# shield.net
KiCad netlist of a schematic drawn in EAGLE
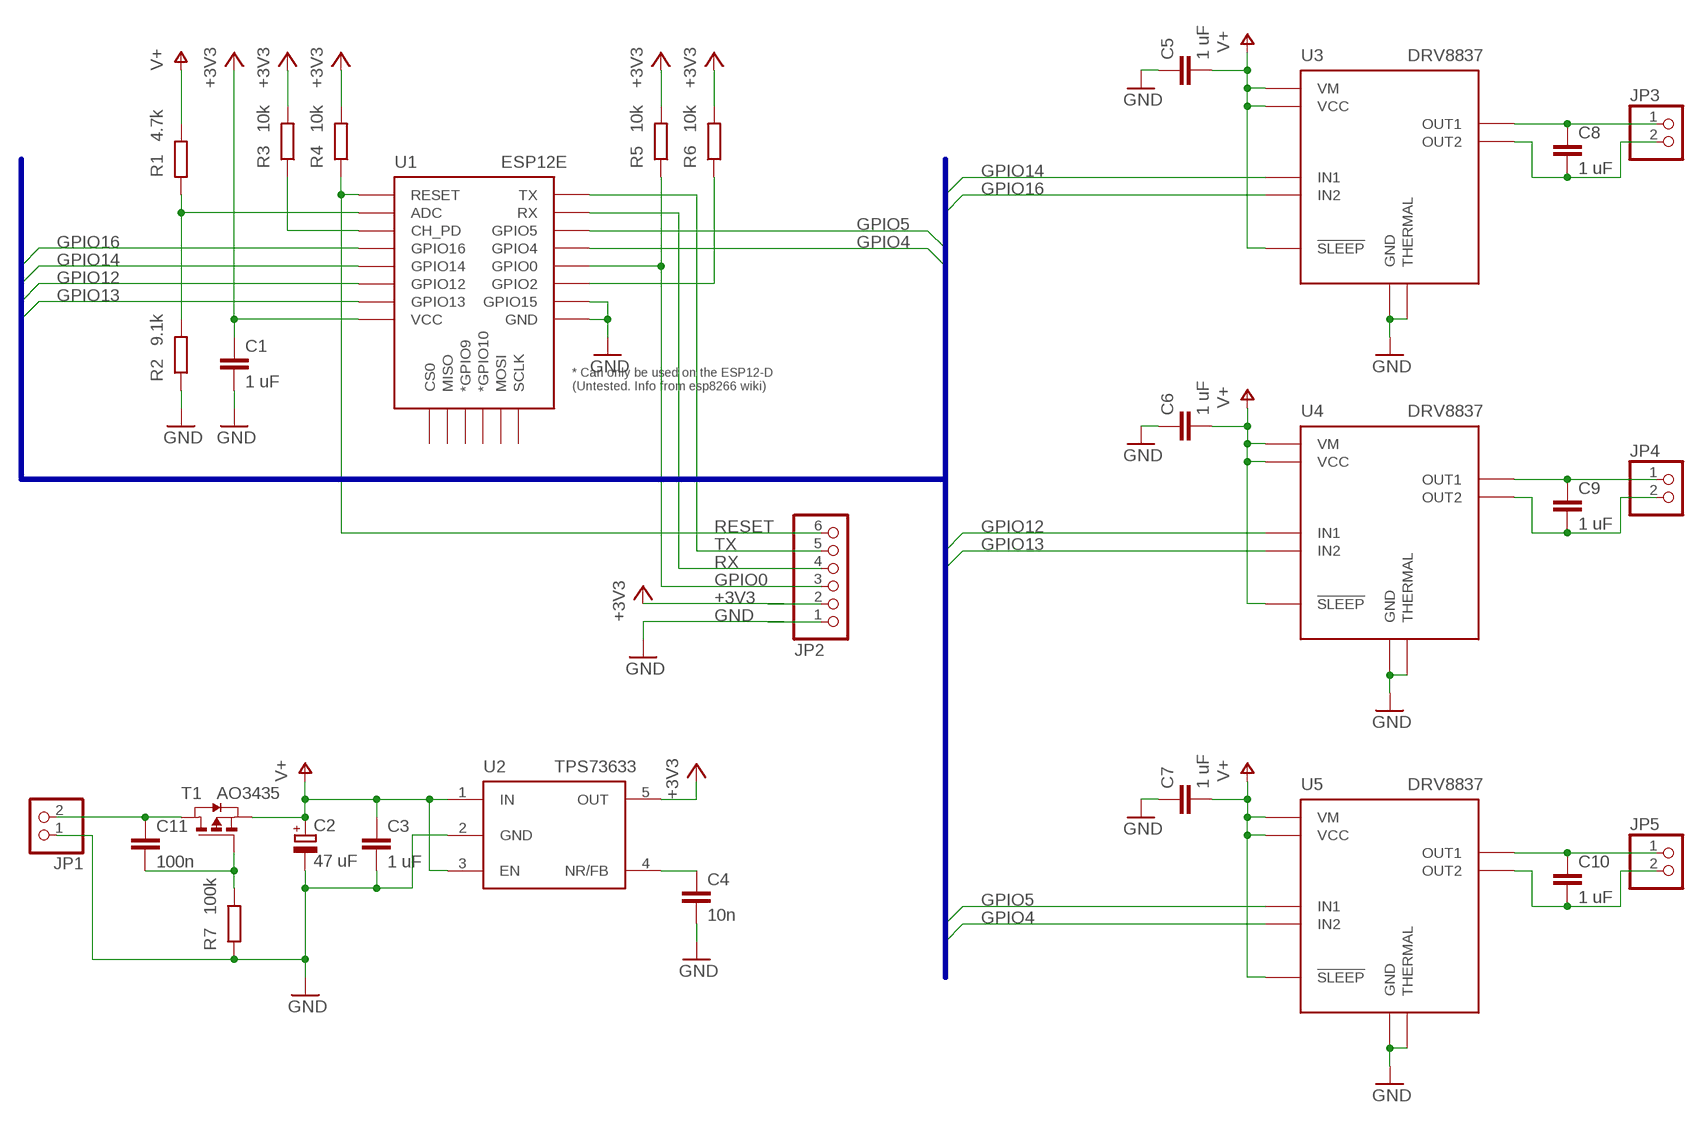
[diagram p0: schematic, sheet 1]

(export (version "E")
  (design (tool "Eeschema 10.0.6"))
  (components
    (comp (ref "C1")
      (value "1 uF")
      (footprint "eagle-import:C0805")
      (libsource (lib "eagle-import") (part "C-EUC0805"))
    )
    (comp (ref "C2")
      (value "47 uF")
      (footprint "eagle-import:SMC_A")
      (libsource (lib "eagle-import") (part "CPOL-EUSMCA"))
    )
    (comp (ref "C3")
      (value "1 uF")
      (footprint "eagle-import:C0805")
      (libsource (lib "eagle-import") (part "C-EUC0805"))
    )
    (comp (ref "C4")
      (value "10n")
      (footprint "eagle-import:C0603")
      (libsource (lib "eagle-import") (part "C-EUC0603"))
    )
    (comp (ref "C5")
      (value "1 uF")
      (footprint "eagle-import:C0805")
      (libsource (lib "eagle-import") (part "C-EUC0805"))
    )
    (comp (ref "C6")
      (value "1 uF")
      (footprint "eagle-import:C0805")
      (libsource (lib "eagle-import") (part "C-EUC0805"))
    )
    (comp (ref "C7")
      (value "1 uF")
      (footprint "eagle-import:C0805")
      (libsource (lib "eagle-import") (part "C-EUC0805"))
    )
    (comp (ref "C8")
      (value "1 uF")
      (footprint "eagle-import:C0805")
      (libsource (lib "eagle-import") (part "C-EUC0805"))
    )
    (comp (ref "C9")
      (value "1 uF")
      (footprint "eagle-import:C0805")
      (libsource (lib "eagle-import") (part "C-EUC0805"))
    )
    (comp (ref "C10")
      (value "1 uF")
      (footprint "eagle-import:C0805")
      (libsource (lib "eagle-import") (part "C-EUC0805"))
    )
    (comp (ref "C11")
      (value "100n")
      (footprint "eagle-import:C0603")
      (libsource (lib "eagle-import") (part "C-EUC0603"))
    )
    (comp (ref "JP1")
      (value "PINHD-1X2")
      (footprint "eagle-import:1X02")
      (libsource (lib "eagle-import") (part "PINHD-1X2"))
    )
    (comp (ref "JP2")
      (value "PINHD-1X6")
      (footprint "eagle-import:1X06")
      (libsource (lib "eagle-import") (part "PINHD-1X6"))
    )
    (comp (ref "JP3")
      (value "PINHD-1X2")
      (footprint "eagle-import:1X02")
      (libsource (lib "eagle-import") (part "PINHD-1X2"))
    )
    (comp (ref "JP4")
      (value "PINHD-1X2")
      (footprint "eagle-import:1X02")
      (libsource (lib "eagle-import") (part "PINHD-1X2"))
    )
    (comp (ref "JP5")
      (value "PINHD-1X2")
      (footprint "eagle-import:1X02")
      (libsource (lib "eagle-import") (part "PINHD-1X2"))
    )
    (comp (ref "R1")
      (value "4.7k")
      (footprint "eagle-import:R0603")
      (libsource (lib "eagle-import") (part "R-EU_R0603"))
    )
    (comp (ref "R2")
      (value "9.1k")
      (footprint "eagle-import:R0603")
      (libsource (lib "eagle-import") (part "R-EU_R0603"))
    )
    (comp (ref "R3")
      (value "10k")
      (footprint "eagle-import:R0603")
      (libsource (lib "eagle-import") (part "R-EU_R0603"))
    )
    (comp (ref "R4")
      (value "10k")
      (footprint "eagle-import:R0603")
      (libsource (lib "eagle-import") (part "R-EU_R0603"))
    )
    (comp (ref "R5")
      (value "10k")
      (footprint "eagle-import:R0603")
      (libsource (lib "eagle-import") (part "R-EU_R0603"))
    )
    (comp (ref "R6")
      (value "10k")
      (footprint "eagle-import:R0603")
      (libsource (lib "eagle-import") (part "R-EU_R0603"))
    )
    (comp (ref "R7")
      (value "100k")
      (footprint "eagle-import:R0603")
      (libsource (lib "eagle-import") (part "R-EU_R0603"))
    )
    (comp (ref "T1")
      (value "AO3435")
      (footprint "eagle-import:SOT-23")
      (libsource (lib "eagle-import") (part "PMOSSOT23"))
    )
    (comp (ref "U1")
      (value "ESP12E")
      (footprint "eagle-import:ESP12E-SMD")
      (libsource (lib "eagle-import") (part "ESP12ESMD"))
    )
    (comp (ref "U2")
      (value "TPS73633")
      (footprint "eagle-import:SOT23-5L")
      (libsource (lib "eagle-import") (part "TPS73633"))
    )
    (comp (ref "U3")
      (value "DRV8837")
      (footprint "eagle-import:QFN8")
      (libsource (lib "eagle-import") (part "DRV8837"))
    )
    (comp (ref "U4")
      (value "DRV8837")
      (footprint "eagle-import:QFN8")
      (libsource (lib "eagle-import") (part "DRV8837"))
    )
    (comp (ref "U5")
      (value "DRV8837")
      (footprint "eagle-import:QFN8")
      (libsource (lib "eagle-import") (part "DRV8837"))
    )
  )
  (nets
    (net (code "1") (name "+3V3") (class "Default")
      (node (ref "C1") (pin "1") (pinfunction "1_1") (pintype "passive"))
      (node (ref "JP2") (pin "2") (pinfunction "2_2") (pintype "passive"))
      (node (ref "R3") (pin "2") (pinfunction "2_2") (pintype "passive"))
      (node (ref "R4") (pin "2") (pinfunction "2_2") (pintype "passive"))
      (node (ref "R5") (pin "2") (pinfunction "2_2") (pintype "passive"))
      (node (ref "R6") (pin "2") (pinfunction "2_2") (pintype "passive"))
      (node (ref "U1") (pin "VCC") (pinfunction "VCC_VCC") (pintype "bidirectional"))
      (node (ref "U2") (pin "5") (pinfunction "OUT_5") (pintype "bidirectional"))
    )
    (net (code "2") (name "/GPIO0") (class "Default")
      (node (ref "JP2") (pin "3") (pinfunction "3_3") (pintype "passive"))
      (node (ref "R5") (pin "1") (pinfunction "1_1") (pintype "passive"))
      (node (ref "U1") (pin "GPIO0") (pinfunction "GPIO0_GPIO0") (pintype "bidirectional"))
    )
    (net (code "3") (name "/GPIO4") (class "Default")
      (node (ref "U1") (pin "GPIO4") (pinfunction "GPIO4_GPIO4") (pintype "bidirectional"))
      (node (ref "U5") (pin "P$5") (pinfunction "IN2_P$5") (pintype "bidirectional"))
    )
    (net (code "4") (name "/GPIO5") (class "Default")
      (node (ref "U1") (pin "GPIO5") (pinfunction "GPIO5_GPIO5") (pintype "bidirectional"))
      (node (ref "U5") (pin "P$6") (pinfunction "IN1_P$6") (pintype "bidirectional"))
    )
    (net (code "5") (name "/GPIO12") (class "Default")
      (node (ref "U1") (pin "GPIO12") (pinfunction "GPIO12_GPIO12") (pintype "bidirectional"))
      (node (ref "U4") (pin "P$6") (pinfunction "IN1_P$6") (pintype "bidirectional"))
    )
    (net (code "6") (name "/GPIO13") (class "Default")
      (node (ref "U1") (pin "GPIO13") (pinfunction "GPIO13_GPIO13") (pintype "bidirectional"))
      (node (ref "U4") (pin "P$5") (pinfunction "IN2_P$5") (pintype "bidirectional"))
    )
    (net (code "7") (name "/GPIO14") (class "Default")
      (node (ref "U1") (pin "GPIO14") (pinfunction "GPIO14_GPIO14") (pintype "bidirectional"))
      (node (ref "U3") (pin "P$6") (pinfunction "IN1_P$6") (pintype "bidirectional"))
    )
    (net (code "8") (name "/GPIO16") (class "Default")
      (node (ref "U1") (pin "GPIO16") (pinfunction "GPIO16_GPIO16") (pintype "bidirectional"))
      (node (ref "U3") (pin "P$5") (pinfunction "IN2_P$5") (pintype "bidirectional"))
    )
    (net (code "9") (name "/RESET") (class "Default")
      (node (ref "JP2") (pin "6") (pinfunction "6_6") (pintype "passive"))
      (node (ref "R4") (pin "1") (pinfunction "1_1") (pintype "passive"))
      (node (ref "U1") (pin "RESET") (pinfunction "RESET_RESET") (pintype "bidirectional"))
    )
    (net (code "10") (name "/RX") (class "Default")
      (node (ref "JP2") (pin "4") (pinfunction "4_4") (pintype "passive"))
      (node (ref "U1") (pin "RXD0") (pinfunction "RX_RXD0") (pintype "bidirectional"))
    )
    (net (code "11") (name "/TX") (class "Default")
      (node (ref "JP2") (pin "5") (pinfunction "5_5") (pintype "passive"))
      (node (ref "U1") (pin "TXD0") (pinfunction "TX_TXD0") (pintype "bidirectional"))
    )
    (net (code "12") (name "GND") (class "Default")
      (node (ref "C1") (pin "2") (pinfunction "2_2") (pintype "passive"))
      (node (ref "C2") (pin "-") (pinfunction "-_-") (pintype "passive"))
      (node (ref "C3") (pin "2") (pinfunction "2_2") (pintype "passive"))
      (node (ref "C4") (pin "2") (pinfunction "2_2") (pintype "passive"))
      (node (ref "C5") (pin "1") (pinfunction "1_1") (pintype "passive"))
      (node (ref "C6") (pin "1") (pinfunction "1_1") (pintype "passive"))
      (node (ref "C7") (pin "1") (pinfunction "1_1") (pintype "passive"))
      (node (ref "JP1") (pin "1") (pinfunction "1_1") (pintype "passive"))
      (node (ref "JP2") (pin "1") (pinfunction "1_1") (pintype "passive"))
      (node (ref "R2") (pin "1") (pinfunction "1_1") (pintype "passive"))
      (node (ref "R7") (pin "1") (pinfunction "1_1") (pintype "passive"))
      (node (ref "U1") (pin "GND") (pinfunction "GND_GND") (pintype "bidirectional"))
      (node (ref "U1") (pin "GPIO15") (pinfunction "GPIO15_GPIO15") (pintype "bidirectional"))
      (node (ref "U2") (pin "2") (pinfunction "GND_2") (pintype "bidirectional"))
      (node (ref "U3") (pin "P$4") (pinfunction "GND_P$4") (pintype "bidirectional"))
      (node (ref "U3") (pin "P$9") (pinfunction "THERMAL_P$9") (pintype "bidirectional"))
      (node (ref "U4") (pin "P$4") (pinfunction "GND_P$4") (pintype "bidirectional"))
      (node (ref "U4") (pin "P$9") (pinfunction "THERMAL_P$9") (pintype "bidirectional"))
      (node (ref "U5") (pin "P$4") (pinfunction "GND_P$4") (pintype "bidirectional"))
      (node (ref "U5") (pin "P$9") (pinfunction "THERMAL_P$9") (pintype "bidirectional"))
    )
    (net (code "13") (name "Net-(R1-Pad1)") (class "Default")
      (node (ref "R1") (pin "1") (pinfunction "1_1") (pintype "passive"))
      (node (ref "R2") (pin "2") (pinfunction "2_2") (pintype "passive"))
      (node (ref "U1") (pin "ADC") (pinfunction "ADC_ADC") (pintype "bidirectional"))
    )
    (net (code "14") (name "Net-(R3-Pad1)") (class "Default")
      (node (ref "R3") (pin "1") (pinfunction "1_1") (pintype "passive"))
      (node (ref "U1") (pin "CH_PD") (pinfunction "CH_PD_CH_PD") (pintype "bidirectional"))
    )
    (net (code "15") (name "Net-(R6-Pad1)") (class "Default")
      (node (ref "R6") (pin "1") (pinfunction "1_1") (pintype "passive"))
      (node (ref "U1") (pin "GPIO2") (pinfunction "GPIO2_GPIO2") (pintype "bidirectional"))
    )
    (net (code "16") (name "Net-(T1-D)") (class "Default")
      (node (ref "C11") (pin "1") (pinfunction "1_1") (pintype "passive"))
      (node (ref "JP1") (pin "2") (pinfunction "2_2") (pintype "passive"))
      (node (ref "T1") (pin "1") (pinfunction "D_1") (pintype "passive"))
    )
    (net (code "17") (name "Net-(T1-G)") (class "Default")
      (node (ref "C11") (pin "2") (pinfunction "2_2") (pintype "passive"))
      (node (ref "R7") (pin "2") (pinfunction "2_2") (pintype "passive"))
      (node (ref "T1") (pin "3") (pinfunction "G_3") (pintype "passive"))
    )
    (net (code "18") (name "Net-(U2-NR{slash}FB)") (class "Default")
      (node (ref "C4") (pin "1") (pinfunction "1_1") (pintype "passive"))
      (node (ref "U2") (pin "4") (pinfunction "NR/FB_4") (pintype "bidirectional"))
    )
    (net (code "19") (name "Net-(U3-OUT1)") (class "Default")
      (node (ref "C8") (pin "1") (pinfunction "1_1") (pintype "passive"))
      (node (ref "JP3") (pin "1") (pinfunction "1_1") (pintype "passive"))
      (node (ref "U3") (pin "P$2") (pinfunction "OUT1_P$2") (pintype "bidirectional"))
    )
    (net (code "20") (name "Net-(U3-OUT2)") (class "Default")
      (node (ref "C8") (pin "2") (pinfunction "2_2") (pintype "passive"))
      (node (ref "JP3") (pin "2") (pinfunction "2_2") (pintype "passive"))
      (node (ref "U3") (pin "P$3") (pinfunction "OUT2_P$3") (pintype "bidirectional"))
    )
    (net (code "21") (name "Net-(U4-OUT1)") (class "Default")
      (node (ref "C9") (pin "1") (pinfunction "1_1") (pintype "passive"))
      (node (ref "JP4") (pin "1") (pinfunction "1_1") (pintype "passive"))
      (node (ref "U4") (pin "P$2") (pinfunction "OUT1_P$2") (pintype "bidirectional"))
    )
    (net (code "22") (name "Net-(U4-OUT2)") (class "Default")
      (node (ref "C9") (pin "2") (pinfunction "2_2") (pintype "passive"))
      (node (ref "JP4") (pin "2") (pinfunction "2_2") (pintype "passive"))
      (node (ref "U4") (pin "P$3") (pinfunction "OUT2_P$3") (pintype "bidirectional"))
    )
    (net (code "23") (name "Net-(U5-OUT1)") (class "Default")
      (node (ref "C10") (pin "1") (pinfunction "1_1") (pintype "passive"))
      (node (ref "JP5") (pin "1") (pinfunction "1_1") (pintype "passive"))
      (node (ref "U5") (pin "P$2") (pinfunction "OUT1_P$2") (pintype "bidirectional"))
    )
    (net (code "24") (name "Net-(U5-OUT2)") (class "Default")
      (node (ref "C10") (pin "2") (pinfunction "2_2") (pintype "passive"))
      (node (ref "JP5") (pin "2") (pinfunction "2_2") (pintype "passive"))
      (node (ref "U5") (pin "P$3") (pinfunction "OUT2_P$3") (pintype "bidirectional"))
    )
    (net (code "25") (name "V+") (class "Default")
      (node (ref "C2") (pin "+") (pinfunction "+_+") (pintype "passive"))
      (node (ref "C3") (pin "1") (pinfunction "1_1") (pintype "passive"))
      (node (ref "C5") (pin "2") (pinfunction "2_2") (pintype "passive"))
      (node (ref "C6") (pin "2") (pinfunction "2_2") (pintype "passive"))
      (node (ref "C7") (pin "2") (pinfunction "2_2") (pintype "passive"))
      (node (ref "R1") (pin "2") (pinfunction "2_2") (pintype "passive"))
      (node (ref "T1") (pin "2") (pinfunction "S_2") (pintype "passive"))
      (node (ref "U2") (pin "1") (pinfunction "IN_1") (pintype "bidirectional"))
      (node (ref "U2") (pin "3") (pinfunction "EN_3") (pintype "bidirectional"))
      (node (ref "U3") (pin "P$1") (pinfunction "VM_P$1") (pintype "bidirectional"))
      (node (ref "U3") (pin "P$7") (pinfunction "~{SLEEP}_P$7") (pintype "bidirectional"))
      (node (ref "U3") (pin "P$8") (pinfunction "VCC_P$8") (pintype "bidirectional"))
      (node (ref "U4") (pin "P$1") (pinfunction "VM_P$1") (pintype "bidirectional"))
      (node (ref "U4") (pin "P$7") (pinfunction "~{SLEEP}_P$7") (pintype "bidirectional"))
      (node (ref "U4") (pin "P$8") (pinfunction "VCC_P$8") (pintype "bidirectional"))
      (node (ref "U5") (pin "P$1") (pinfunction "VM_P$1") (pintype "bidirectional"))
      (node (ref "U5") (pin "P$7") (pinfunction "~{SLEEP}_P$7") (pintype "bidirectional"))
      (node (ref "U5") (pin "P$8") (pinfunction "VCC_P$8") (pintype "bidirectional"))
    )
    (net (code "26") (name "unconnected-(U1-*GPIO9-PadGPIO9)") (class "Default")
      (node (ref "U1") (pin "GPIO9") (pinfunction "*GPIO9_GPIO9") (pintype "bidirectional"))
    )
    (net (code "27") (name "unconnected-(U1-*GPIO10-PadGPIO10)") (class "Default")
      (node (ref "U1") (pin "GPIO10") (pinfunction "*GPIO10_GPIO10") (pintype "bidirectional"))
    )
    (net (code "28") (name "unconnected-(U1-PadCS0)") (class "Default")
      (node (ref "U1") (pin "CS0") (pinfunction "CS0_CS0") (pintype "bidirectional"))
    )
    (net (code "29") (name "unconnected-(U1-PadMISO)") (class "Default")
      (node (ref "U1") (pin "MISO") (pinfunction "MISO_MISO") (pintype "bidirectional"))
    )
    (net (code "30") (name "unconnected-(U1-PadMOSI)") (class "Default")
      (node (ref "U1") (pin "MOSI") (pinfunction "MOSI_MOSI") (pintype "bidirectional"))
    )
    (net (code "31") (name "unconnected-(U1-PadSCLK)") (class "Default")
      (node (ref "U1") (pin "SCLK") (pinfunction "SCLK_SCLK") (pintype "bidirectional"))
    )
  )
)
